# pi_sainsmart_relay.net
KiCad netlist of a schematic drawn in EAGLE
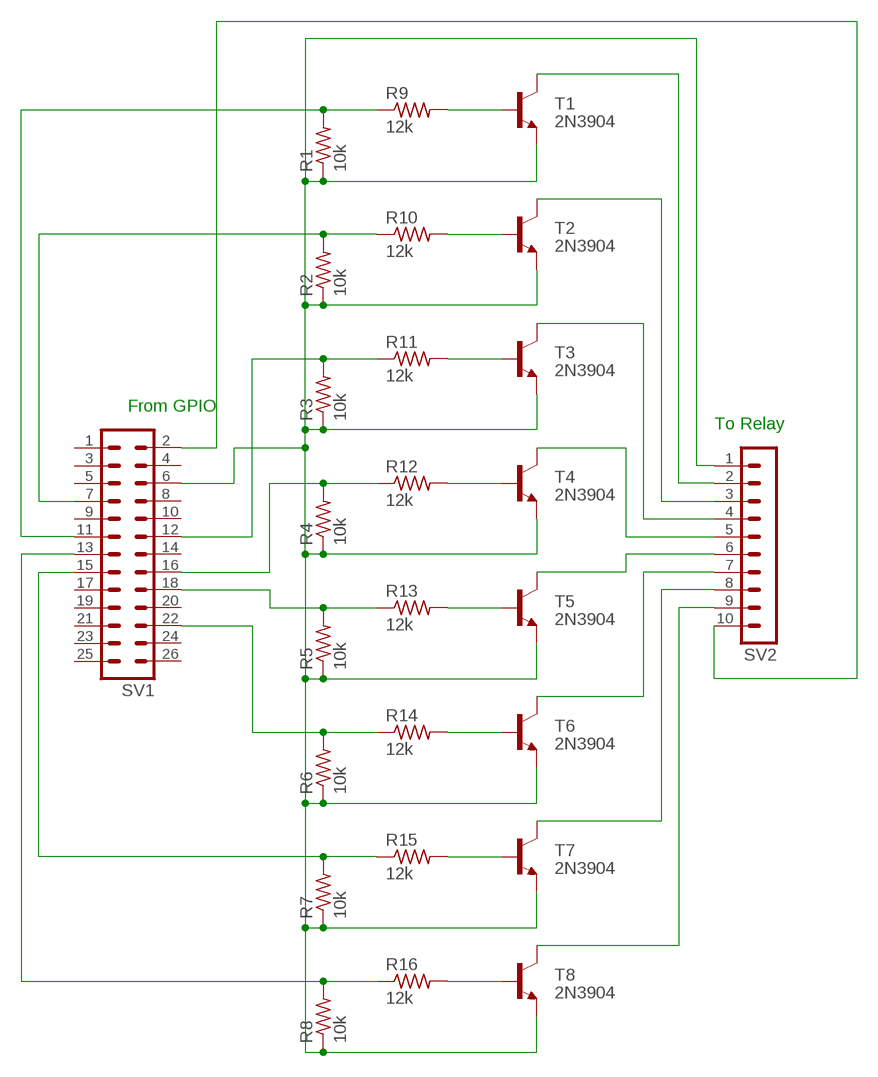
[diagram p0: schematic, sheet 1]

(export (version "E")
  (design (tool "Eeschema 10.0.6"))
  (components
    (comp (ref "R1")
      (value "10k")
      (footprint "eagle-import:0204V")
      (libsource (lib "eagle-import") (part "R-US_0204/2V"))
    )
    (comp (ref "R2")
      (value "10k")
      (footprint "eagle-import:0204V")
      (libsource (lib "eagle-import") (part "R-US_0204/2V"))
    )
    (comp (ref "R3")
      (value "10k")
      (footprint "eagle-import:0204V")
      (libsource (lib "eagle-import") (part "R-US_0204/2V"))
    )
    (comp (ref "R4")
      (value "10k")
      (footprint "eagle-import:0204V")
      (libsource (lib "eagle-import") (part "R-US_0204/2V"))
    )
    (comp (ref "R5")
      (value "10k")
      (footprint "eagle-import:0204V")
      (libsource (lib "eagle-import") (part "R-US_0204/2V"))
    )
    (comp (ref "R6")
      (value "10k")
      (footprint "eagle-import:0204V")
      (libsource (lib "eagle-import") (part "R-US_0204/2V"))
    )
    (comp (ref "R7")
      (value "10k")
      (footprint "eagle-import:0204V")
      (libsource (lib "eagle-import") (part "R-US_0204/2V"))
    )
    (comp (ref "R8")
      (value "10k")
      (footprint "eagle-import:0204V")
      (libsource (lib "eagle-import") (part "R-US_0204/2V"))
    )
    (comp (ref "R9")
      (value "12k")
      (footprint "eagle-import:0207_12")
      (libsource (lib "eagle-import") (part "R-US_0207/12"))
    )
    (comp (ref "R10")
      (value "12k")
      (footprint "eagle-import:0207_12")
      (libsource (lib "eagle-import") (part "R-US_0207/12"))
    )
    (comp (ref "R11")
      (value "12k")
      (footprint "eagle-import:0207_12")
      (libsource (lib "eagle-import") (part "R-US_0207/12"))
    )
    (comp (ref "R12")
      (value "12k")
      (footprint "eagle-import:0207_12")
      (libsource (lib "eagle-import") (part "R-US_0207/12"))
    )
    (comp (ref "R13")
      (value "12k")
      (footprint "eagle-import:0207_12")
      (libsource (lib "eagle-import") (part "R-US_0207/12"))
    )
    (comp (ref "R14")
      (value "12k")
      (footprint "eagle-import:0207_12")
      (libsource (lib "eagle-import") (part "R-US_0207/12"))
    )
    (comp (ref "R15")
      (value "12k")
      (footprint "eagle-import:0207_12")
      (libsource (lib "eagle-import") (part "R-US_0207/12"))
    )
    (comp (ref "R16")
      (value "12k")
      (footprint "eagle-import:0207_12")
      (libsource (lib "eagle-import") (part "R-US_0207/12"))
    )
    (comp (ref "SV1")
      (value "MA13-2")
      (footprint "eagle-import:MA13-2")
      (libsource (lib "eagle-import") (part "MA13-2"))
    )
    (comp (ref "SV2")
      (value "MA10-1")
      (footprint "eagle-import:MA10-1")
      (libsource (lib "eagle-import") (part "MA10-1"))
    )
    (comp (ref "T1")
      (value "2N3904")
      (footprint "eagle-import:TO92-EBC")
      (libsource (lib "eagle-import") (part "-NPN-TO92-EBC"))
    )
    (comp (ref "T2")
      (value "2N3904")
      (footprint "eagle-import:TO92-EBC")
      (libsource (lib "eagle-import") (part "-NPN-TO92-EBC"))
    )
    (comp (ref "T3")
      (value "2N3904")
      (footprint "eagle-import:TO92-EBC")
      (libsource (lib "eagle-import") (part "-NPN-TO92-EBC"))
    )
    (comp (ref "T4")
      (value "2N3904")
      (footprint "eagle-import:TO92-EBC")
      (libsource (lib "eagle-import") (part "-NPN-TO92-EBC"))
    )
    (comp (ref "T5")
      (value "2N3904")
      (footprint "eagle-import:TO92-EBC")
      (libsource (lib "eagle-import") (part "-NPN-TO92-EBC"))
    )
    (comp (ref "T6")
      (value "2N3904")
      (footprint "eagle-import:TO92-EBC")
      (libsource (lib "eagle-import") (part "-NPN-TO92-EBC"))
    )
    (comp (ref "T7")
      (value "2N3904")
      (footprint "eagle-import:TO92-EBC")
      (libsource (lib "eagle-import") (part "-NPN-TO92-EBC"))
    )
    (comp (ref "T8")
      (value "2N3904")
      (footprint "eagle-import:TO92-EBC")
      (libsource (lib "eagle-import") (part "-NPN-TO92-EBC"))
    )
  )
  (nets
    (net (code "1") (name "Net-(R1-Pad1)") (class "Default")
      (node (ref "R1") (pin "1") (pinfunction "1_1") (pintype "passive"))
      (node (ref "R2") (pin "1") (pinfunction "1_1") (pintype "passive"))
      (node (ref "R3") (pin "1") (pinfunction "1_1") (pintype "passive"))
      (node (ref "R4") (pin "1") (pinfunction "1_1") (pintype "passive"))
      (node (ref "R5") (pin "1") (pinfunction "1_1") (pintype "passive"))
      (node (ref "R6") (pin "1") (pinfunction "1_1") (pintype "passive"))
      (node (ref "R7") (pin "1") (pinfunction "1_1") (pintype "passive"))
      (node (ref "R8") (pin "1") (pinfunction "1_1") (pintype "passive"))
      (node (ref "SV1") (pin "6") (pinfunction "6_6") (pintype "passive"))
      (node (ref "SV2") (pin "1") (pinfunction "1_1") (pintype "passive"))
      (node (ref "T1") (pin "E") (pinfunction "E_E") (pintype "passive"))
      (node (ref "T2") (pin "E") (pinfunction "E_E") (pintype "passive"))
      (node (ref "T3") (pin "E") (pinfunction "E_E") (pintype "passive"))
      (node (ref "T4") (pin "E") (pinfunction "E_E") (pintype "passive"))
      (node (ref "T5") (pin "E") (pinfunction "E_E") (pintype "passive"))
      (node (ref "T6") (pin "E") (pinfunction "E_E") (pintype "passive"))
      (node (ref "T7") (pin "E") (pinfunction "E_E") (pintype "passive"))
      (node (ref "T8") (pin "E") (pinfunction "E_E") (pintype "passive"))
    )
    (net (code "2") (name "Net-(R1-Pad2)") (class "Default")
      (node (ref "R1") (pin "2") (pinfunction "2_2") (pintype "passive"))
      (node (ref "R9") (pin "1") (pinfunction "1_1") (pintype "passive"))
      (node (ref "SV1") (pin "11") (pinfunction "11_11") (pintype "passive"))
    )
    (net (code "3") (name "Net-(R9-Pad2)") (class "Default")
      (node (ref "R9") (pin "2") (pinfunction "2_2") (pintype "passive"))
      (node (ref "T1") (pin "B") (pinfunction "B_B") (pintype "passive"))
    )
    (net (code "4") (name "Net-(R10-Pad1)") (class "Default")
      (node (ref "R10") (pin "1") (pinfunction "1_1") (pintype "passive"))
      (node (ref "R2") (pin "2") (pinfunction "2_2") (pintype "passive"))
      (node (ref "SV1") (pin "7") (pinfunction "7_7") (pintype "passive"))
    )
    (net (code "5") (name "Net-(R10-Pad2)") (class "Default")
      (node (ref "R10") (pin "2") (pinfunction "2_2") (pintype "passive"))
      (node (ref "T2") (pin "B") (pinfunction "B_B") (pintype "passive"))
    )
    (net (code "6") (name "Net-(R11-Pad1)") (class "Default")
      (node (ref "R11") (pin "1") (pinfunction "1_1") (pintype "passive"))
      (node (ref "R3") (pin "2") (pinfunction "2_2") (pintype "passive"))
      (node (ref "SV1") (pin "12") (pinfunction "12_12") (pintype "passive"))
    )
    (net (code "7") (name "Net-(R11-Pad2)") (class "Default")
      (node (ref "R11") (pin "2") (pinfunction "2_2") (pintype "passive"))
      (node (ref "T3") (pin "B") (pinfunction "B_B") (pintype "passive"))
    )
    (net (code "8") (name "Net-(R12-Pad1)") (class "Default")
      (node (ref "R12") (pin "1") (pinfunction "1_1") (pintype "passive"))
      (node (ref "R4") (pin "2") (pinfunction "2_2") (pintype "passive"))
      (node (ref "SV1") (pin "16") (pinfunction "16_16") (pintype "passive"))
    )
    (net (code "9") (name "Net-(R12-Pad2)") (class "Default")
      (node (ref "R12") (pin "2") (pinfunction "2_2") (pintype "passive"))
      (node (ref "T4") (pin "B") (pinfunction "B_B") (pintype "passive"))
    )
    (net (code "10") (name "Net-(R13-Pad1)") (class "Default")
      (node (ref "R13") (pin "1") (pinfunction "1_1") (pintype "passive"))
      (node (ref "R5") (pin "2") (pinfunction "2_2") (pintype "passive"))
      (node (ref "SV1") (pin "18") (pinfunction "18_18") (pintype "passive"))
    )
    (net (code "11") (name "Net-(R13-Pad2)") (class "Default")
      (node (ref "R13") (pin "2") (pinfunction "2_2") (pintype "passive"))
      (node (ref "T5") (pin "B") (pinfunction "B_B") (pintype "passive"))
    )
    (net (code "12") (name "Net-(R14-Pad1)") (class "Default")
      (node (ref "R14") (pin "1") (pinfunction "1_1") (pintype "passive"))
      (node (ref "R6") (pin "2") (pinfunction "2_2") (pintype "passive"))
      (node (ref "SV1") (pin "22") (pinfunction "22_22") (pintype "passive"))
    )
    (net (code "13") (name "Net-(R14-Pad2)") (class "Default")
      (node (ref "R14") (pin "2") (pinfunction "2_2") (pintype "passive"))
      (node (ref "T6") (pin "B") (pinfunction "B_B") (pintype "passive"))
    )
    (net (code "14") (name "Net-(R15-Pad1)") (class "Default")
      (node (ref "R15") (pin "1") (pinfunction "1_1") (pintype "passive"))
      (node (ref "R7") (pin "2") (pinfunction "2_2") (pintype "passive"))
      (node (ref "SV1") (pin "15") (pinfunction "15_15") (pintype "passive"))
    )
    (net (code "15") (name "Net-(R15-Pad2)") (class "Default")
      (node (ref "R15") (pin "2") (pinfunction "2_2") (pintype "passive"))
      (node (ref "T7") (pin "B") (pinfunction "B_B") (pintype "passive"))
    )
    (net (code "16") (name "Net-(R16-Pad1)") (class "Default")
      (node (ref "R16") (pin "1") (pinfunction "1_1") (pintype "passive"))
      (node (ref "R8") (pin "2") (pinfunction "2_2") (pintype "passive"))
      (node (ref "SV1") (pin "13") (pinfunction "13_13") (pintype "passive"))
    )
    (net (code "17") (name "Net-(R16-Pad2)") (class "Default")
      (node (ref "R16") (pin "2") (pinfunction "2_2") (pintype "passive"))
      (node (ref "T8") (pin "B") (pinfunction "B_B") (pintype "passive"))
    )
    (net (code "18") (name "Net-(SV1-Pad2)") (class "Default")
      (node (ref "SV1") (pin "2") (pinfunction "2_2") (pintype "passive"))
      (node (ref "SV2") (pin "10") (pinfunction "10_10") (pintype "passive"))
    )
    (net (code "19") (name "Net-(SV2-Pad2)") (class "Default")
      (node (ref "SV2") (pin "2") (pinfunction "2_2") (pintype "passive"))
      (node (ref "T1") (pin "C") (pinfunction "C_C") (pintype "passive"))
    )
    (net (code "20") (name "Net-(SV2-Pad3)") (class "Default")
      (node (ref "SV2") (pin "3") (pinfunction "3_3") (pintype "passive"))
      (node (ref "T2") (pin "C") (pinfunction "C_C") (pintype "passive"))
    )
    (net (code "21") (name "Net-(SV2-Pad4)") (class "Default")
      (node (ref "SV2") (pin "4") (pinfunction "4_4") (pintype "passive"))
      (node (ref "T3") (pin "C") (pinfunction "C_C") (pintype "passive"))
    )
    (net (code "22") (name "Net-(SV2-Pad5)") (class "Default")
      (node (ref "SV2") (pin "5") (pinfunction "5_5") (pintype "passive"))
      (node (ref "T4") (pin "C") (pinfunction "C_C") (pintype "passive"))
    )
    (net (code "23") (name "Net-(SV2-Pad6)") (class "Default")
      (node (ref "SV2") (pin "6") (pinfunction "6_6") (pintype "passive"))
      (node (ref "T5") (pin "C") (pinfunction "C_C") (pintype "passive"))
    )
    (net (code "24") (name "Net-(SV2-Pad7)") (class "Default")
      (node (ref "SV2") (pin "7") (pinfunction "7_7") (pintype "passive"))
      (node (ref "T6") (pin "C") (pinfunction "C_C") (pintype "passive"))
    )
    (net (code "25") (name "Net-(SV2-Pad8)") (class "Default")
      (node (ref "SV2") (pin "8") (pinfunction "8_8") (pintype "passive"))
      (node (ref "T7") (pin "C") (pinfunction "C_C") (pintype "passive"))
    )
    (net (code "26") (name "Net-(SV2-Pad9)") (class "Default")
      (node (ref "SV2") (pin "9") (pinfunction "9_9") (pintype "passive"))
      (node (ref "T8") (pin "C") (pinfunction "C_C") (pintype "passive"))
    )
    (net (code "27") (name "unconnected-(SV1-Pad1)") (class "Default")
      (node (ref "SV1") (pin "1") (pinfunction "1_1") (pintype "passive"))
    )
    (net (code "28") (name "unconnected-(SV1-Pad3)") (class "Default")
      (node (ref "SV1") (pin "3") (pinfunction "3_3") (pintype "passive"))
    )
    (net (code "29") (name "unconnected-(SV1-Pad4)") (class "Default")
      (node (ref "SV1") (pin "4") (pinfunction "4_4") (pintype "passive"))
    )
    (net (code "30") (name "unconnected-(SV1-Pad5)") (class "Default")
      (node (ref "SV1") (pin "5") (pinfunction "5_5") (pintype "passive"))
    )
    (net (code "31") (name "unconnected-(SV1-Pad8)") (class "Default")
      (node (ref "SV1") (pin "8") (pinfunction "8_8") (pintype "passive"))
    )
    (net (code "32") (name "unconnected-(SV1-Pad9)") (class "Default")
      (node (ref "SV1") (pin "9") (pinfunction "9_9") (pintype "passive"))
    )
    (net (code "33") (name "unconnected-(SV1-Pad10)") (class "Default")
      (node (ref "SV1") (pin "10") (pinfunction "10_10") (pintype "passive"))
    )
    (net (code "34") (name "unconnected-(SV1-Pad14)") (class "Default")
      (node (ref "SV1") (pin "14") (pinfunction "14_14") (pintype "passive"))
    )
    (net (code "35") (name "unconnected-(SV1-Pad17)") (class "Default")
      (node (ref "SV1") (pin "17") (pinfunction "17_17") (pintype "passive"))
    )
    (net (code "36") (name "unconnected-(SV1-Pad19)") (class "Default")
      (node (ref "SV1") (pin "19") (pinfunction "19_19") (pintype "passive"))
    )
    (net (code "37") (name "unconnected-(SV1-Pad20)") (class "Default")
      (node (ref "SV1") (pin "20") (pinfunction "20_20") (pintype "passive"))
    )
    (net (code "38") (name "unconnected-(SV1-Pad21)") (class "Default")
      (node (ref "SV1") (pin "21") (pinfunction "21_21") (pintype "passive"))
    )
    (net (code "39") (name "unconnected-(SV1-Pad23)") (class "Default")
      (node (ref "SV1") (pin "23") (pinfunction "23_23") (pintype "passive"))
    )
    (net (code "40") (name "unconnected-(SV1-Pad24)") (class "Default")
      (node (ref "SV1") (pin "24") (pinfunction "24_24") (pintype "passive"))
    )
    (net (code "41") (name "unconnected-(SV1-Pad25)") (class "Default")
      (node (ref "SV1") (pin "25") (pinfunction "25_25") (pintype "passive"))
    )
    (net (code "42") (name "unconnected-(SV1-Pad26)") (class "Default")
      (node (ref "SV1") (pin "26") (pinfunction "26_26") (pintype "passive"))
    )
  )
)
